# Plasma_Speaker_SMD_For_recording.net
KiCad netlist of a schematic drawn in Altium Designer
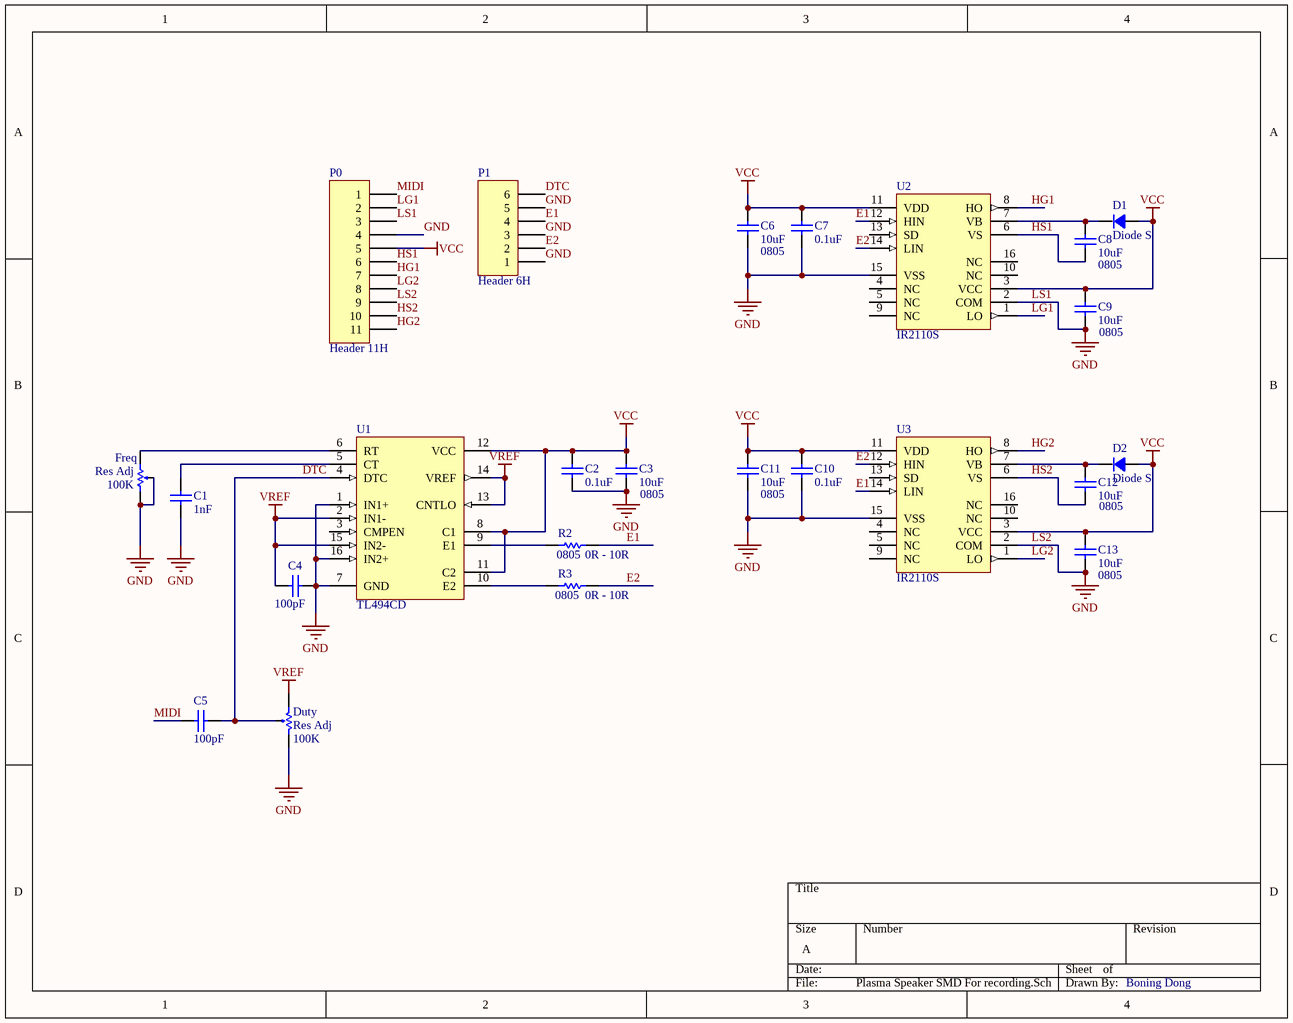
[diagram p0: Plasma Speaker SMD For recording.SchDoc]

(export (version "E")
  (design (tool "Eeschema 10.0.6"))
  (components
    (comp (ref "C1")
      (value "1nF")
      (footprint "D0603")
      (description "Capacitor")
      (fields (field (name "Comment") "0603") (field (name "PUBLISHER") "Altium Limited"))
      (libsource (lib "Miscellaneous Devices") (part "Cap"))
    )
    (comp (ref "C2")
      (value "0.1uF")
      (footprint "D0603")
      (description "Capacitor")
      (fields (field (name "Comment") "0603") (field (name "PUBLISHER") "Altium Limited"))
      (libsource (lib "Miscellaneous Devices") (part "Cap"))
    )
    (comp (ref "C3")
      (value "0805")
      (footprint "D0805")
      (description "Capacitor")
      (fields (field (name "ALTIUM_VALUE") "10uF") (field (name "PUBLISHER") "Altium Limited"))
      (libsource (lib "Miscellaneous Devices") (part "Cap"))
    )
    (comp (ref "C4")
      (value "100pF")
      (footprint "D0603")
      (description "Capacitor")
      (fields (field (name "Comment") "0603") (field (name "PUBLISHER") "Altium Limited"))
      (libsource (lib "Miscellaneous Devices") (part "Cap"))
    )
    (comp (ref "C5")
      (value "100pF")
      (footprint "D0603")
      (description "Capacitor")
      (fields (field (name "Comment") "0603") (field (name "PUBLISHER") "Altium Limited"))
      (libsource (lib "Miscellaneous Devices") (part "Cap"))
    )
    (comp (ref "C6")
      (value "0805")
      (footprint "D0805")
      (description "Capacitor")
      (fields (field (name "ALTIUM_VALUE") "10uF") (field (name "PUBLISHER") "Altium Limited"))
      (libsource (lib "Miscellaneous Devices") (part "Cap"))
    )
    (comp (ref "C7")
      (value "0.1uF")
      (footprint "D0603")
      (description "Capacitor")
      (fields (field (name "Comment") "0603") (field (name "PUBLISHER") "Altium Limited"))
      (libsource (lib "Miscellaneous Devices") (part "Cap"))
    )
    (comp (ref "C8")
      (value "0805")
      (footprint "D0805")
      (description "Capacitor")
      (fields (field (name "ALTIUM_VALUE") "10uF") (field (name "PUBLISHER") "Altium Limited"))
      (libsource (lib "Miscellaneous Devices") (part "Cap"))
    )
    (comp (ref "C9")
      (value "0805")
      (footprint "D0805")
      (description "Capacitor")
      (fields (field (name "ALTIUM_VALUE") "10uF") (field (name "PUBLISHER") "Altium Limited"))
      (libsource (lib "Miscellaneous Devices") (part "Cap"))
    )
    (comp (ref "C10")
      (value "0.1uF")
      (footprint "D0603")
      (description "Capacitor")
      (fields (field (name "Comment") "0603") (field (name "PUBLISHER") "Altium Limited"))
      (libsource (lib "Miscellaneous Devices") (part "Cap"))
    )
    (comp (ref "C11")
      (value "0805")
      (footprint "D0805")
      (description "Capacitor")
      (fields (field (name "ALTIUM_VALUE") "10uF") (field (name "PUBLISHER") "Altium Limited"))
      (libsource (lib "Miscellaneous Devices") (part "Cap"))
    )
    (comp (ref "C12")
      (value "0805")
      (footprint "D0805")
      (description "Capacitor")
      (fields (field (name "ALTIUM_VALUE") "10uF") (field (name "PUBLISHER") "Altium Limited"))
      (libsource (lib "Miscellaneous Devices") (part "Cap"))
    )
    (comp (ref "C13")
      (value "0805")
      (footprint "D0805")
      (description "Capacitor")
      (fields (field (name "ALTIUM_VALUE") "10uF") (field (name "PUBLISHER") "Altium Limited"))
      (libsource (lib "Miscellaneous Devices") (part "Cap"))
    )
    (comp (ref "D1")
      (value "Diode S")
      (footprint "DO-214")
      (description "Zener Diode")
      (fields (field (name "PUBLISHER") "Altium Limited"))
      (libsource (lib "Miscellaneous Devices") (part "Diode S"))
    )
    (comp (ref "D2")
      (value "Diode S")
      (footprint "DO-214")
      (description "Zener Diode")
      (fields (field (name "PUBLISHER") "Altium Limited"))
      (libsource (lib "Miscellaneous Devices") (part "Diode S"))
    )
    (comp (ref "Duty")
      (value "Res Adj")
      (footprint "RES-3362P")
      (description "Resistor")
      (fields (field (name "ALTIUM_VALUE") "100K") (field (name "PUBLISHER") "Altium Limited"))
      (libsource (lib "Miscellaneous Devices") (part "Res Adj"))
    )
    (comp (ref "Freq")
      (value "Res Adj")
      (footprint "RES-3362P")
      (description "Resistor")
      (fields (field (name "ALTIUM_VALUE") "100K") (field (name "PUBLISHER") "Altium Limited"))
      (libsource (lib "Miscellaneous Devices") (part "Res Adj"))
    )
    (comp (ref "P0")
      (value "Header 11H")
      (footprint "HDR1X11H")
      (description "Header, 11-Pin, Right Angle")
      (fields (field (name "PUBLISHER") "Altium Limited"))
      (libsource (lib "Miscellaneous Connectors") (part "Header 11H"))
    )
    (comp (ref "P1")
      (value "Header 6H")
      (footprint "HDR1X6H")
      (description "Header, 6-Pin, Right Angle")
      (fields (field (name "PUBLISHER") "Altium Limited"))
      (libsource (lib "Miscellaneous Connectors") (part "Header 6H"))
    )
    (comp (ref "R2")
      (value "0805")
      (footprint "D0805")
      (description "Resistor")
      (fields (field (name "ALTIUM_VALUE") "0R - 10R") (field (name "PUBLISHER") "Altium Limited"))
      (libsource (lib "Miscellaneous Devices") (part "Res1"))
    )
    (comp (ref "R3")
      (value "0805")
      (footprint "D0805")
      (description "Resistor")
      (fields (field (name "ALTIUM_VALUE") "0R - 10R") (field (name "PUBLISHER") "Altium Limited"))
      (libsource (lib "Miscellaneous Devices") (part "Res1"))
    )
    (comp (ref "U1")
      (value "TL494CD")
      (footprint "751B-05_N")
      (description "Switchmode Pulse Width Modulation Control Circuit")
      (fields (field (name "PUBLISHER") "Altium Limited"))
      (libsource (lib "ON Semi Power Mgt SMPS Controller") (part "TL494CD"))
    )
    (comp (ref "U2")
      (value "IR2110S")
      (footprint "SOIC16_N")
      (description "High and Low Side Driver")
      (fields (field (name "PUBLISHER") "Altium Limited"))
      (libsource (lib "IR Interface Bridge Driver") (part "IR2110S"))
    )
    (comp (ref "U3")
      (value "IR2110S")
      (footprint "SOIC16_N")
      (description "High and Low Side Driver")
      (fields (field (name "PUBLISHER") "Altium Limited"))
      (libsource (lib "IR Interface Bridge Driver") (part "IR2110S"))
    )
  )
  (nets
    (net (code "1") (name "/DTC") (class "Default")
      (node (ref "C5") (pin "2") (pinfunction "2_2") (pintype "passive"))
      (node (ref "Duty") (pin "2") (pinfunction "2_2") (pintype "passive"))
      (node (ref "P1") (pin "6") (pinfunction "6_6") (pintype "passive"))
      (node (ref "U1") (pin "4") (pinfunction "DTC_4") (pintype "input"))
    )
    (net (code "2") (name "/E1") (class "Default")
      (node (ref "P1") (pin "4") (pinfunction "4_4") (pintype "passive"))
      (node (ref "R2") (pin "1") (pinfunction "1_1") (pintype "passive"))
      (node (ref "U2") (pin "12") (pinfunction "HIN_12") (pintype "input"))
      (node (ref "U3") (pin "14") (pinfunction "LIN_14") (pintype "input"))
    )
    (net (code "3") (name "/E2") (class "Default")
      (node (ref "P1") (pin "2") (pinfunction "2_2") (pintype "passive"))
      (node (ref "R3") (pin "1") (pinfunction "1_1") (pintype "passive"))
      (node (ref "U2") (pin "14") (pinfunction "LIN_14") (pintype "input"))
      (node (ref "U3") (pin "12") (pinfunction "HIN_12") (pintype "input"))
    )
    (net (code "4") (name "/HG1") (class "Default")
      (node (ref "P0") (pin "7") (pinfunction "7_7") (pintype "passive"))
      (node (ref "U2") (pin "8") (pinfunction "HO_8") (pintype "output"))
    )
    (net (code "5") (name "/HG2") (class "Default")
      (node (ref "P0") (pin "11") (pinfunction "11_11") (pintype "passive"))
      (node (ref "U3") (pin "8") (pinfunction "HO_8") (pintype "output"))
    )
    (net (code "6") (name "/HS1") (class "Default")
      (node (ref "C8") (pin "1") (pinfunction "1_1") (pintype "passive"))
      (node (ref "P0") (pin "6") (pinfunction "6_6") (pintype "passive"))
      (node (ref "U2") (pin "6") (pinfunction "VS_6") (pintype "power_in"))
    )
    (net (code "7") (name "/HS2") (class "Default")
      (node (ref "C12") (pin "1") (pinfunction "1_1") (pintype "passive"))
      (node (ref "P0") (pin "10") (pinfunction "10_10") (pintype "passive"))
      (node (ref "U3") (pin "6") (pinfunction "VS_6") (pintype "power_in"))
    )
    (net (code "8") (name "/LG1") (class "Default")
      (node (ref "P0") (pin "2") (pinfunction "2_2") (pintype "passive"))
      (node (ref "U2") (pin "1") (pinfunction "LO_1") (pintype "output"))
    )
    (net (code "9") (name "/LG2") (class "Default")
      (node (ref "P0") (pin "8") (pinfunction "8_8") (pintype "passive"))
      (node (ref "U3") (pin "1") (pinfunction "LO_1") (pintype "output"))
    )
    (net (code "10") (name "/MIDI") (class "Default")
      (node (ref "C5") (pin "1") (pinfunction "1_1") (pintype "passive"))
      (node (ref "P0") (pin "1") (pinfunction "1_1") (pintype "passive"))
    )
    (net (code "11") (name "GND") (class "Default")
      (node (ref "C1") (pin "1") (pinfunction "1_1") (pintype "passive"))
      (node (ref "C10") (pin "1") (pinfunction "1_1") (pintype "passive"))
      (node (ref "C11") (pin "1") (pinfunction "1_1") (pintype "passive"))
      (node (ref "C13") (pin "1") (pinfunction "1_1") (pintype "passive"))
      (node (ref "C2") (pin "1") (pinfunction "1_1") (pintype "passive"))
      (node (ref "C3") (pin "1") (pinfunction "1_1") (pintype "passive"))
      (node (ref "C4") (pin "1") (pinfunction "1_1") (pintype "passive"))
      (node (ref "C6") (pin "1") (pinfunction "1_1") (pintype "passive"))
      (node (ref "C7") (pin "1") (pinfunction "1_1") (pintype "passive"))
      (node (ref "C9") (pin "1") (pinfunction "1_1") (pintype "passive"))
      (node (ref "Duty") (pin "3") (pinfunction "3_3") (pintype "passive"))
      (node (ref "Freq") (pin "2") (pinfunction "2_2") (pintype "passive"))
      (node (ref "Freq") (pin "3") (pinfunction "3_3") (pintype "passive"))
      (node (ref "P0") (pin "3") (pinfunction "3_3") (pintype "passive"))
      (node (ref "P0") (pin "4") (pinfunction "4_4") (pintype "passive"))
      (node (ref "P0") (pin "9") (pinfunction "9_9") (pintype "passive"))
      (node (ref "P1") (pin "1") (pinfunction "1_1") (pintype "passive"))
      (node (ref "P1") (pin "3") (pinfunction "3_3") (pintype "passive"))
      (node (ref "P1") (pin "5") (pinfunction "5_5") (pintype "passive"))
      (node (ref "U1") (pin "1") (pinfunction "IN1+_1") (pintype "input"))
      (node (ref "U1") (pin "16") (pinfunction "IN2+_16") (pintype "input"))
      (node (ref "U1") (pin "7") (pinfunction "GND_7") (pintype "power_in"))
      (node (ref "U2") (pin "15") (pinfunction "VSS_15") (pintype "power_in"))
      (node (ref "U2") (pin "2") (pinfunction "COM_2") (pintype "power_in"))
      (node (ref "U3") (pin "15") (pinfunction "VSS_15") (pintype "power_in"))
      (node (ref "U3") (pin "2") (pinfunction "COM_2") (pintype "power_in"))
    )
    (net (code "12") (name "Net-(U1-CT)") (class "Default")
      (node (ref "C1") (pin "2") (pinfunction "2_2") (pintype "passive"))
      (node (ref "U1") (pin "5") (pinfunction "CT_5") (pintype "passive"))
    )
    (net (code "13") (name "Net-(U1-E1)") (class "Default")
      (node (ref "R2") (pin "2") (pinfunction "2_2") (pintype "passive"))
      (node (ref "U1") (pin "9") (pinfunction "E1_9") (pintype "passive"))
    )
    (net (code "14") (name "Net-(U1-E2)") (class "Default")
      (node (ref "R3") (pin "2") (pinfunction "2_2") (pintype "passive"))
      (node (ref "U1") (pin "10") (pinfunction "E2_10") (pintype "passive"))
    )
    (net (code "15") (name "Net-(U1-RT)") (class "Default")
      (node (ref "Freq") (pin "1") (pinfunction "1_1") (pintype "passive"))
      (node (ref "U1") (pin "6") (pinfunction "RT_6") (pintype "passive"))
    )
    (net (code "16") (name "Net-(U2-VB)") (class "Default")
      (node (ref "C8") (pin "2") (pinfunction "2_2") (pintype "passive"))
      (node (ref "D1") (pin "2") (pinfunction "2_2") (pintype "passive"))
      (node (ref "U2") (pin "7") (pinfunction "VB_7") (pintype "power_in"))
    )
    (net (code "17") (name "Net-(U3-VB)") (class "Default")
      (node (ref "C12") (pin "2") (pinfunction "2_2") (pintype "passive"))
      (node (ref "D2") (pin "2") (pinfunction "2_2") (pintype "passive"))
      (node (ref "U3") (pin "7") (pinfunction "VB_7") (pintype "power_in"))
    )
    (net (code "18") (name "VCC") (class "Default")
      (node (ref "C10") (pin "2") (pinfunction "2_2") (pintype "passive"))
      (node (ref "C11") (pin "2") (pinfunction "2_2") (pintype "passive"))
      (node (ref "C13") (pin "2") (pinfunction "2_2") (pintype "passive"))
      (node (ref "C2") (pin "2") (pinfunction "2_2") (pintype "passive"))
      (node (ref "C3") (pin "2") (pinfunction "2_2") (pintype "passive"))
      (node (ref "C6") (pin "2") (pinfunction "2_2") (pintype "passive"))
      (node (ref "C7") (pin "2") (pinfunction "2_2") (pintype "passive"))
      (node (ref "C9") (pin "2") (pinfunction "2_2") (pintype "passive"))
      (node (ref "D1") (pin "1") (pinfunction "1_1") (pintype "passive"))
      (node (ref "D2") (pin "1") (pinfunction "1_1") (pintype "passive"))
      (node (ref "P0") (pin "5") (pinfunction "5_5") (pintype "passive"))
      (node (ref "U1") (pin "11") (pinfunction "C2_11") (pintype "passive"))
      (node (ref "U1") (pin "12") (pinfunction "VCC_12") (pintype "power_in"))
      (node (ref "U1") (pin "8") (pinfunction "C1_8") (pintype "passive"))
      (node (ref "U2") (pin "11") (pinfunction "VDD_11") (pintype "power_in"))
      (node (ref "U2") (pin "3") (pinfunction "VCC_3") (pintype "power_in"))
      (node (ref "U3") (pin "11") (pinfunction "VDD_11") (pintype "power_in"))
      (node (ref "U3") (pin "3") (pinfunction "VCC_3") (pintype "power_in"))
    )
    (net (code "19") (name "VREF") (class "Default")
      (node (ref "C4") (pin "2") (pinfunction "2_2") (pintype "passive"))
      (node (ref "Duty") (pin "1") (pinfunction "1_1") (pintype "passive"))
      (node (ref "U1") (pin "13") (pinfunction "CNTLO_13") (pintype "input"))
      (node (ref "U1") (pin "14") (pinfunction "VREF_14") (pintype "output"))
      (node (ref "U1") (pin "15") (pinfunction "IN2-_15") (pintype "input"))
      (node (ref "U1") (pin "2") (pinfunction "IN1-_2") (pintype "input"))
    )
    (net (code "20") (name "unconnected-(U1-CMPEN-Pad3)") (class "Default")
      (node (ref "U1") (pin "3") (pinfunction "CMPEN_3") (pintype "input"))
    )
    (net (code "21") (name "unconnected-(U2-NC-Pad4)") (class "Default")
      (node (ref "U2") (pin "4") (pinfunction "NC_4") (pintype "passive"))
    )
    (net (code "22") (name "unconnected-(U2-NC-Pad5)") (class "Default")
      (node (ref "U2") (pin "5") (pinfunction "NC_5") (pintype "passive"))
    )
    (net (code "23") (name "unconnected-(U2-NC-Pad9)") (class "Default")
      (node (ref "U2") (pin "9") (pinfunction "NC_9") (pintype "passive"))
    )
    (net (code "24") (name "unconnected-(U2-NC-Pad10)") (class "Default")
      (node (ref "U2") (pin "10") (pinfunction "NC_10") (pintype "passive"))
    )
    (net (code "25") (name "unconnected-(U2-NC-Pad16)") (class "Default")
      (node (ref "U2") (pin "16") (pinfunction "NC_16") (pintype "passive"))
    )
    (net (code "26") (name "unconnected-(U2-SD-Pad13)") (class "Default")
      (node (ref "U2") (pin "13") (pinfunction "SD_13") (pintype "input"))
    )
    (net (code "27") (name "unconnected-(U3-NC-Pad4)") (class "Default")
      (node (ref "U3") (pin "4") (pinfunction "NC_4") (pintype "passive"))
    )
    (net (code "28") (name "unconnected-(U3-NC-Pad5)") (class "Default")
      (node (ref "U3") (pin "5") (pinfunction "NC_5") (pintype "passive"))
    )
    (net (code "29") (name "unconnected-(U3-NC-Pad9)") (class "Default")
      (node (ref "U3") (pin "9") (pinfunction "NC_9") (pintype "passive"))
    )
    (net (code "30") (name "unconnected-(U3-NC-Pad10)") (class "Default")
      (node (ref "U3") (pin "10") (pinfunction "NC_10") (pintype "passive"))
    )
    (net (code "31") (name "unconnected-(U3-NC-Pad16)") (class "Default")
      (node (ref "U3") (pin "16") (pinfunction "NC_16") (pintype "passive"))
    )
    (net (code "32") (name "unconnected-(U3-SD-Pad13)") (class "Default")
      (node (ref "U3") (pin "13") (pinfunction "SD_13") (pintype "input"))
    )
  )
)
